# eeZee_Crystal.net
KiCad netlist of a schematic drawn in EAGLE
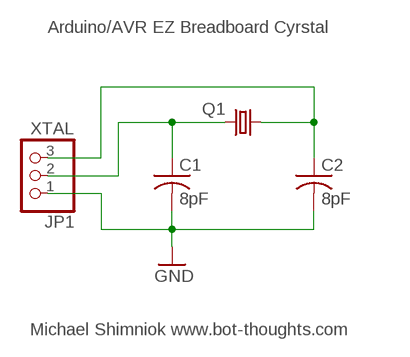
[diagram p0: schematic, sheet 1]

(export (version "E")
  (design (tool "Eeschema 10.0.6"))
  (components
    (comp (ref "C1")
      (value "8pF")
      (footprint "eagle-import:C0603")
      (fields (field (name "PARTNO") "C1608C0G1H080D"))
      (libsource (lib "eagle-import") (part "C-USC0603"))
    )
    (comp (ref "C2")
      (value "8pF")
      (footprint "eagle-import:C0603")
      (fields (field (name "PARTNO") "C1608C0G1H080D"))
      (libsource (lib "eagle-import") (part "C-USC0603"))
    )
    (comp (ref "JP1")
      (value "XTAL")
      (footprint "eagle-import:1X03-S")
      (libsource (lib "eagle-import") (part "PINHD-1X03_2.54-S"))
    )
    (comp (ref "Q1")
      (value "CRYSTALNDK5X3")
      (footprint "eagle-import:NDK_2PAD_5X3")
      (fields (field (name "PARTNO") "NX5032GA-16.000000MHZ-LN-CD-1"))
      (libsource (lib "eagle-import") (part "CRYSTALNDK5X3"))
    )
  )
  (nets
    (net (code "1") (name "GND") (class "Default")
      (node (ref "C1") (pin "2") (pinfunction "2_2") (pintype "passive"))
      (node (ref "C2") (pin "2") (pinfunction "2_2") (pintype "passive"))
      (node (ref "JP1") (pin "1") (pinfunction "1_1") (pintype "passive"))
    )
    (net (code "2") (name "Net-(Q1-1)") (class "Default")
      (node (ref "C2") (pin "1") (pinfunction "1_1") (pintype "passive"))
      (node (ref "JP1") (pin "3") (pinfunction "3_3") (pintype "passive"))
      (node (ref "Q1") (pin "P$1") (pinfunction "1_P$1") (pintype "passive"))
    )
    (net (code "3") (name "Net-(Q1-2)") (class "Default")
      (node (ref "C1") (pin "1") (pinfunction "1_1") (pintype "passive"))
      (node (ref "JP1") (pin "2") (pinfunction "2_2") (pintype "passive"))
      (node (ref "Q1") (pin "P$2") (pinfunction "2_P$2") (pintype "passive"))
    )
  )
)
